# power_node.net
KiCad netlist of a schematic drawn in EAGLE
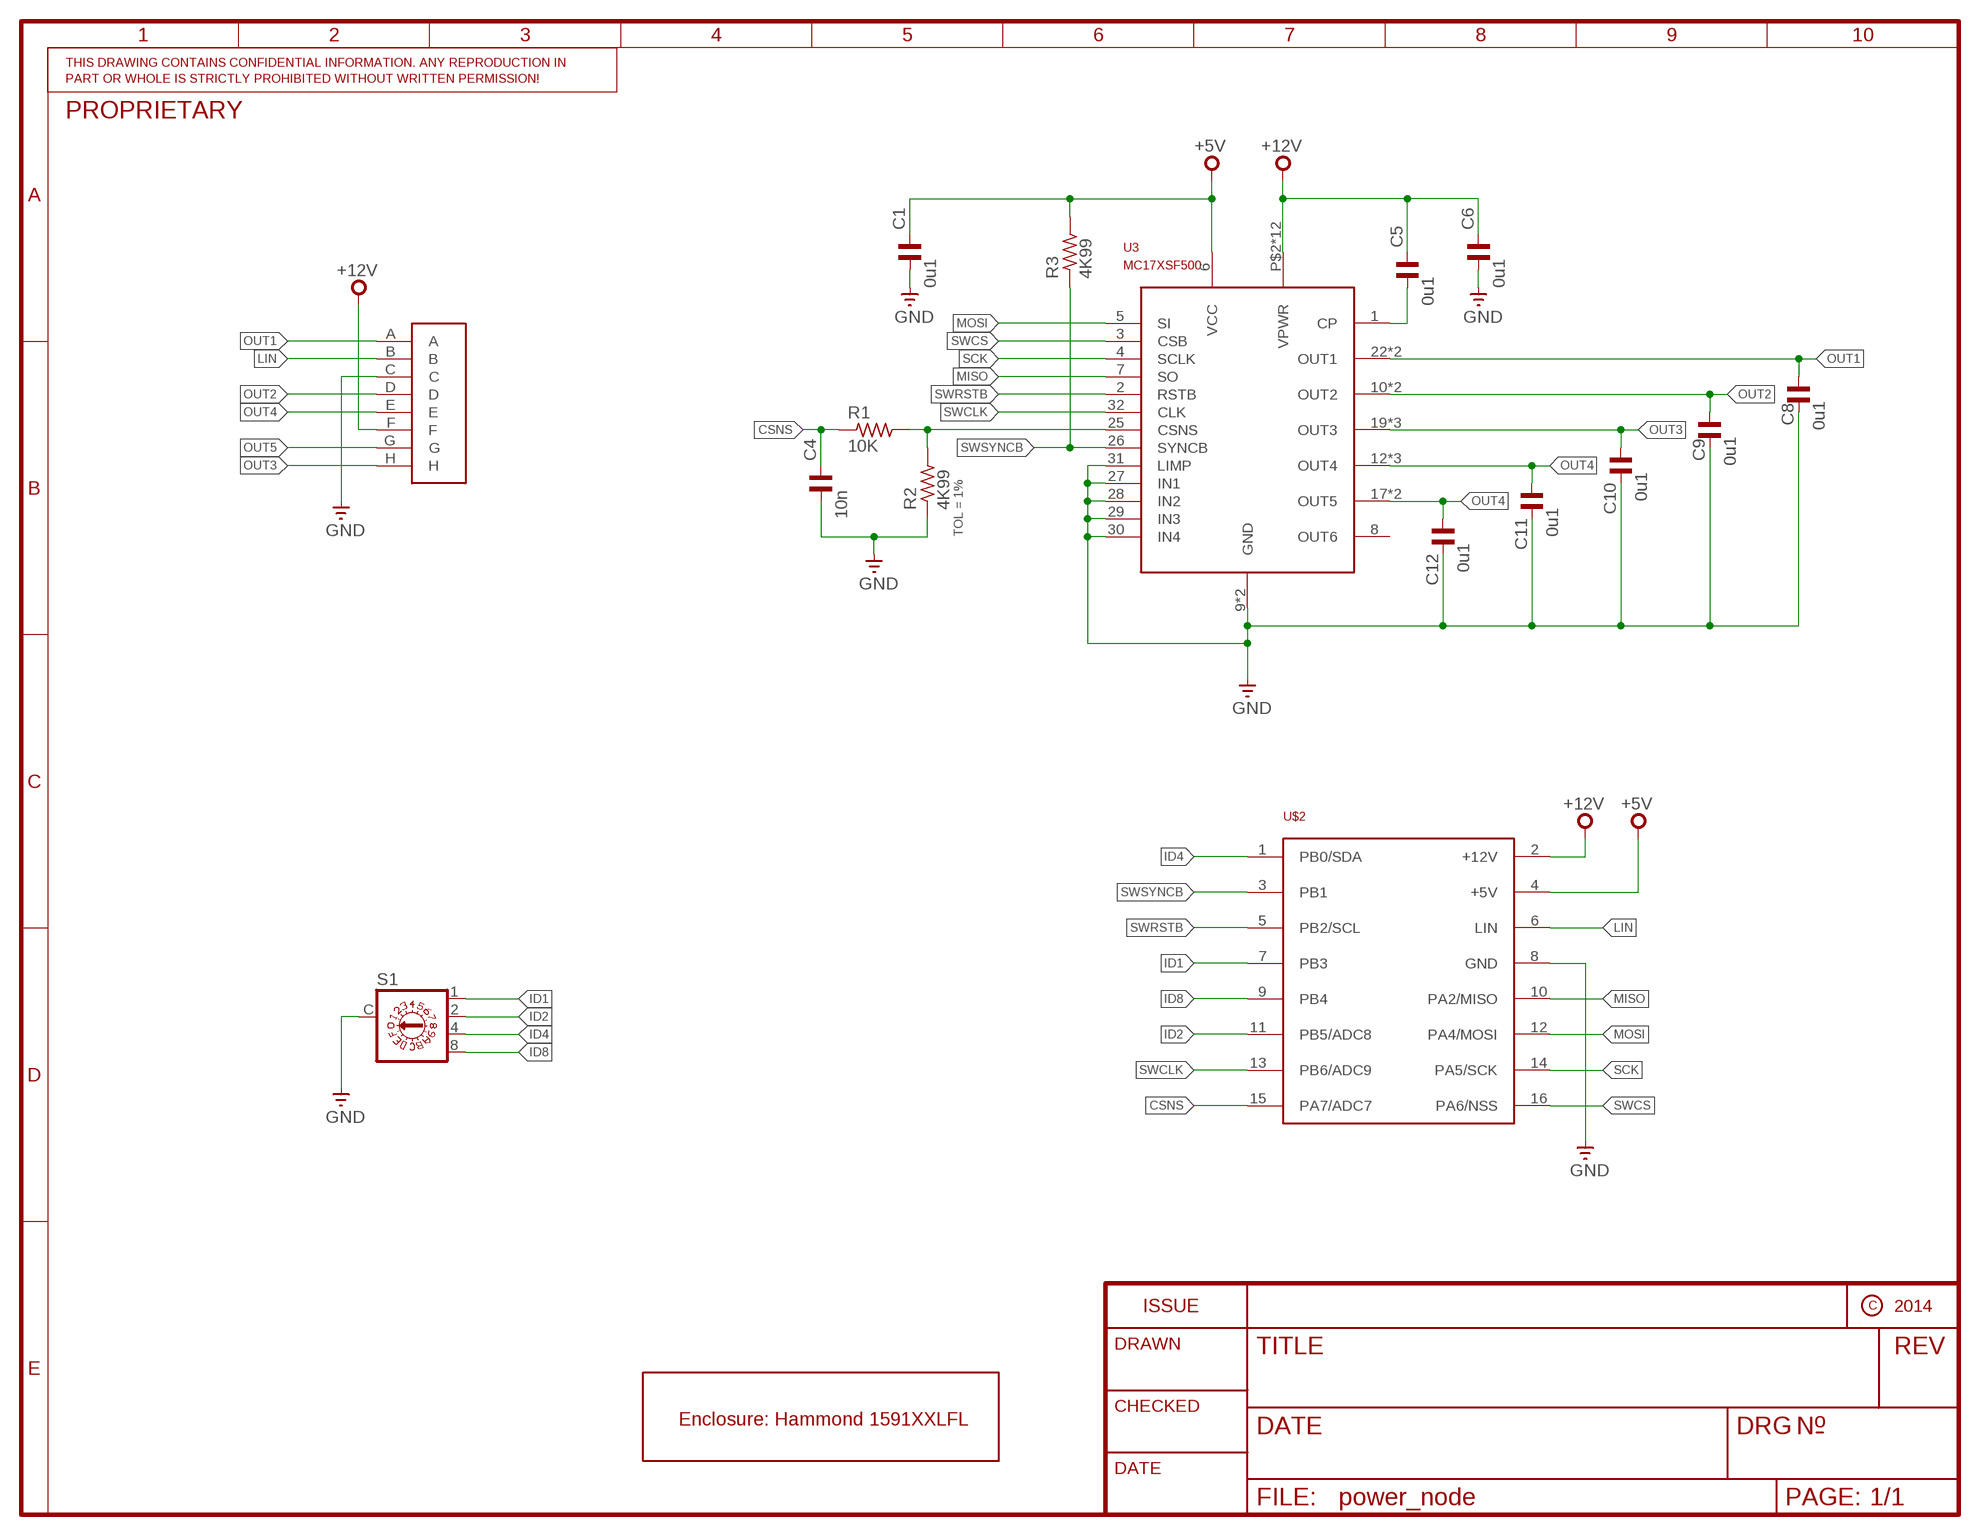
[diagram p0: schematic, sheet 1]

(export (version "E")
  (design (tool "Eeschema 10.0.6"))
  (components
    (comp (ref "C1")
      (value "0u1")
      (footprint "eagle-import:C0805K")
      (fields (field (name "PARTNO") "FK28X7R1H104K"))
      (libsource (lib "eagle-import") (part "C-EUC0805K"))
    )
    (comp (ref "C4")
      (value "10n")
      (footprint "eagle-import:C0805K")
      (fields (field (name "PARTNO") "FK18X7R1H103K"))
      (libsource (lib "eagle-import") (part "C-EUC0805K"))
    )
    (comp (ref "C5")
      (value "0u1")
      (footprint "eagle-import:C0805K")
      (fields (field (name "PARTNO") "FK28X7R1H104K"))
      (libsource (lib "eagle-import") (part "C-EUC0805K"))
    )
    (comp (ref "C6")
      (value "0u1")
      (footprint "eagle-import:C0805K")
      (fields (field (name "PARTNO") "FK28X7R1H104K"))
      (libsource (lib "eagle-import") (part "C-EUC0805K"))
    )
    (comp (ref "C8")
      (value "0u1")
      (footprint "eagle-import:C0805K")
      (fields (field (name "PARTNO") "C1608X7R1H104M080AA"))
      (libsource (lib "eagle-import") (part "C-EUC0805K"))
    )
    (comp (ref "C9")
      (value "0u1")
      (footprint "eagle-import:C0805K")
      (fields (field (name "PARTNO") "C1608X7R1H104M080AA"))
      (libsource (lib "eagle-import") (part "C-EUC0805K"))
    )
    (comp (ref "C10")
      (value "0u1")
      (footprint "eagle-import:C0805K")
      (fields (field (name "PARTNO") "C1608X7R1H104M080AA"))
      (libsource (lib "eagle-import") (part "C-EUC0805K"))
    )
    (comp (ref "C11")
      (value "0u1")
      (footprint "eagle-import:C0805K")
      (fields (field (name "PARTNO") "C1608X7R1H104M080AA"))
      (libsource (lib "eagle-import") (part "C-EUC0805K"))
    )
    (comp (ref "C12")
      (value "0u1")
      (footprint "eagle-import:C0805K")
      (fields (field (name "PARTNO") "C1608X7R1H104M080AA"))
      (libsource (lib "eagle-import") (part "C-EUC0805K"))
    )
    (comp (ref "J2")
      (value "12146734")
      (footprint "eagle-import:12146734")
      (fields (field (name "PARTNO") "12146724-B"))
      (libsource (lib "eagle-import") (part "12146734"))
    )
    (comp (ref "R1")
      (value "10K")
      (footprint "eagle-import:R0805W")
      (fields (field (name "PARTNO") "CF14JT10K0"))
      (libsource (lib "eagle-import") (part "R-EU_R0805W"))
    )
    (comp (ref "R2")
      (value "4K99")
      (footprint "eagle-import:R0805W")
      (fields (field (name "PARTNO") "MFR-25FBF52-4K99") (field (name "TOL") "1%"))
      (libsource (lib "eagle-import") (part "R-EU_R0805W"))
    )
    (comp (ref "R3")
      (value "4K99")
      (footprint "eagle-import:R0805W")
      (fields (field (name "PARTNO") "MFR-25FBF52-4K99"))
      (libsource (lib "eagle-import") (part "R-EU_R0805W"))
    )
    (comp (ref "S1")
      (value "P103")
      (footprint "eagle-import:P103")
      (fields (field (name "PARTNO") "SH-7050MC"))
      (libsource (lib "eagle-import") (part "P103"))
    )
    (comp (ref "U$1")
      (value "1591XXLFL")
      (footprint "eagle-import:1591XXLFL")
      (fields (field (name "PARTNO") "1591XXLFLBK"))
      (libsource (lib "eagle-import") (part "1591XXLFL"))
    )
    (comp (ref "U$2")
      (value "LIN_NODEHORIZ")
      (footprint "eagle-import:LIN_NODE")
      (libsource (lib "eagle-import") (part "LIN_NODEHORIZ"))
    )
    (comp (ref "U3")
      (value "MC17XSF500")
      (footprint "eagle-import:SOIC32W-EP")
      (fields (field (name "PARTNO") "MC17XSF500EK"))
      (libsource (lib "eagle-import") (part "MC17XSF500"))
    )
  )
  (nets
    (net (code "1") (name "+5V") (class "Default")
      (node (ref "C1") (pin "1") (pinfunction "1_1") (pintype "passive"))
      (node (ref "R3") (pin "2") (pinfunction "2_2") (pintype "passive"))
      (node (ref "U$2") (pin "4") (pinfunction "+5V_4") (pintype "power_in"))
      (node (ref "U3") (pin "6") (pinfunction "VCC_6") (pintype "power_in"))
    )
    (net (code "2") (name "+12V") (class "Default")
      (node (ref "C5") (pin "1") (pinfunction "1_1") (pintype "passive"))
      (node (ref "C6") (pin "1") (pinfunction "1_1") (pintype "passive"))
      (node (ref "J2") (pin "F") (pinfunction "F_F") (pintype "bidirectional"))
      (node (ref "U$2") (pin "2") (pinfunction "+12V_2") (pintype "power_in"))
      (node (ref "U3") (pin "P$10") (pinfunction "VPWR_P$10") (pintype "power_in"))
      (node (ref "U3") (pin "P$11") (pinfunction "VPWR_P$11") (pintype "power_in"))
      (node (ref "U3") (pin "P$12") (pinfunction "VPWR_P$12") (pintype "power_in"))
      (node (ref "U3") (pin "P$13") (pinfunction "VPWR_P$13") (pintype "power_in"))
      (node (ref "U3") (pin "P$2") (pinfunction "VPWR_P$2") (pintype "power_in"))
      (node (ref "U3") (pin "P$3") (pinfunction "VPWR_P$3") (pintype "power_in"))
      (node (ref "U3") (pin "P$4") (pinfunction "VPWR_P$4") (pintype "power_in"))
      (node (ref "U3") (pin "P$5") (pinfunction "VPWR_P$5") (pintype "power_in"))
      (node (ref "U3") (pin "P$6") (pinfunction "VPWR_P$6") (pintype "power_in"))
      (node (ref "U3") (pin "P$7") (pinfunction "VPWR_P$7") (pintype "power_in"))
      (node (ref "U3") (pin "P$8") (pinfunction "VPWR_P$8") (pintype "power_in"))
      (node (ref "U3") (pin "P$9") (pinfunction "VPWR_P$9") (pintype "power_in"))
    )
    (net (code "3") (name "CSNS") (class "Default")
      (node (ref "C4") (pin "1") (pinfunction "1_1") (pintype "passive"))
      (node (ref "R1") (pin "1") (pinfunction "1_1") (pintype "passive"))
      (node (ref "U$2") (pin "15") (pinfunction "PA7/ADC7_15") (pintype "bidirectional"))
    )
    (net (code "4") (name "GND") (class "Default")
      (node (ref "C1") (pin "2") (pinfunction "2_2") (pintype "passive"))
      (node (ref "C10") (pin "2") (pinfunction "2_2") (pintype "passive"))
      (node (ref "C11") (pin "2") (pinfunction "2_2") (pintype "passive"))
      (node (ref "C12") (pin "2") (pinfunction "2_2") (pintype "passive"))
      (node (ref "C4") (pin "2") (pinfunction "2_2") (pintype "passive"))
      (node (ref "C6") (pin "2") (pinfunction "2_2") (pintype "passive"))
      (node (ref "C8") (pin "2") (pinfunction "2_2") (pintype "passive"))
      (node (ref "C9") (pin "2") (pinfunction "2_2") (pintype "passive"))
      (node (ref "J2") (pin "C") (pinfunction "C_C") (pintype "bidirectional"))
      (node (ref "R2") (pin "1") (pinfunction "1_1") (pintype "passive"))
      (node (ref "S1") (pin "C") (pinfunction "C_C") (pintype "passive"))
      (node (ref "U$2") (pin "8") (pinfunction "GND_8") (pintype "power_in"))
      (node (ref "U3") (pin "24") (pinfunction "GND_24") (pintype "power_in"))
      (node (ref "U3") (pin "27") (pinfunction "IN1_27") (pintype "input"))
      (node (ref "U3") (pin "28") (pinfunction "IN2_28") (pintype "input"))
      (node (ref "U3") (pin "29") (pinfunction "IN3_29") (pintype "input"))
      (node (ref "U3") (pin "30") (pinfunction "IN4_30") (pintype "input"))
      (node (ref "U3") (pin "31") (pinfunction "LIMP_31") (pintype "input"))
      (node (ref "U3") (pin "9") (pinfunction "GND_9") (pintype "power_in"))
    )
    (net (code "5") (name "ID1") (class "Default")
      (node (ref "S1") (pin "1") (pinfunction "1_1") (pintype "passive"))
      (node (ref "U$2") (pin "7") (pinfunction "PB3_7") (pintype "bidirectional"))
    )
    (net (code "6") (name "ID2") (class "Default")
      (node (ref "S1") (pin "2") (pinfunction "2_2") (pintype "passive"))
      (node (ref "U$2") (pin "11") (pinfunction "PB5/ADC8_11") (pintype "bidirectional"))
    )
    (net (code "7") (name "ID4") (class "Default")
      (node (ref "S1") (pin "4") (pinfunction "4_4") (pintype "passive"))
      (node (ref "U$2") (pin "1") (pinfunction "PB0/SDA_1") (pintype "bidirectional"))
    )
    (net (code "8") (name "ID8") (class "Default")
      (node (ref "S1") (pin "8") (pinfunction "8_8") (pintype "passive"))
      (node (ref "U$2") (pin "9") (pinfunction "PB4_9") (pintype "bidirectional"))
    )
    (net (code "9") (name "LIN") (class "Default")
      (node (ref "J2") (pin "B") (pinfunction "B_B") (pintype "bidirectional"))
      (node (ref "U$2") (pin "6") (pinfunction "LIN_6") (pintype "bidirectional"))
    )
    (net (code "10") (name "MISO") (class "Default")
      (node (ref "U$2") (pin "10") (pinfunction "PA2/MISO_10") (pintype "bidirectional"))
      (node (ref "U3") (pin "7") (pinfunction "SO_7") (pintype "output"))
    )
    (net (code "11") (name "MOSI") (class "Default")
      (node (ref "U$2") (pin "12") (pinfunction "PA4/MOSI_12") (pintype "bidirectional"))
      (node (ref "U3") (pin "5") (pinfunction "SI_5") (pintype "input"))
    )
    (net (code "12") (name "Net-(U3-CP)") (class "Default")
      (node (ref "C5") (pin "2") (pinfunction "2_2") (pintype "passive"))
      (node (ref "U3") (pin "1") (pinfunction "CP_1") (pintype "passive"))
    )
    (net (code "13") (name "Net-(U3-CSNS)") (class "Default")
      (node (ref "R1") (pin "2") (pinfunction "2_2") (pintype "passive"))
      (node (ref "R2") (pin "2") (pinfunction "2_2") (pintype "passive"))
      (node (ref "U3") (pin "25") (pinfunction "CSNS_25") (pintype "output"))
    )
    (net (code "14") (name "OUT1") (class "Default")
      (node (ref "C8") (pin "1") (pinfunction "1_1") (pintype "passive"))
      (node (ref "J2") (pin "A") (pinfunction "A_A") (pintype "bidirectional"))
      (node (ref "U3") (pin "22") (pinfunction "OUT1_22") (pintype "output"))
      (node (ref "U3") (pin "23") (pinfunction "OUT1_23") (pintype "output"))
    )
    (net (code "15") (name "OUT2") (class "Default")
      (node (ref "C9") (pin "1") (pinfunction "1_1") (pintype "passive"))
      (node (ref "J2") (pin "D") (pinfunction "D_D") (pintype "bidirectional"))
      (node (ref "U3") (pin "10") (pinfunction "OUT2_10") (pintype "output"))
      (node (ref "U3") (pin "11") (pinfunction "OUT2_11") (pintype "output"))
    )
    (net (code "16") (name "OUT3") (class "Default")
      (node (ref "C10") (pin "1") (pinfunction "1_1") (pintype "passive"))
      (node (ref "J2") (pin "H") (pinfunction "H_H") (pintype "bidirectional"))
      (node (ref "U3") (pin "19") (pinfunction "OUT3_19") (pintype "output"))
      (node (ref "U3") (pin "20") (pinfunction "OUT3_20") (pintype "output"))
      (node (ref "U3") (pin "21") (pinfunction "OUT3_21") (pintype "output"))
    )
    (net (code "17") (name "OUT4") (class "Default")
      (node (ref "C11") (pin "1") (pinfunction "1_1") (pintype "passive"))
      (node (ref "J2") (pin "E") (pinfunction "E_E") (pintype "bidirectional"))
      (node (ref "U3") (pin "12") (pinfunction "OUT4_12") (pintype "output"))
      (node (ref "U3") (pin "13") (pinfunction "OUT4_13") (pintype "output"))
      (node (ref "U3") (pin "14") (pinfunction "OUT4_14") (pintype "output"))
    )
    (net (code "18") (name "OUT5") (class "Default")
      (node (ref "C12") (pin "1") (pinfunction "1_1") (pintype "passive"))
      (node (ref "J2") (pin "G") (pinfunction "G_G") (pintype "bidirectional"))
      (node (ref "U3") (pin "17") (pinfunction "OUT5_17") (pintype "output"))
      (node (ref "U3") (pin "18") (pinfunction "OUT5_18") (pintype "output"))
    )
    (net (code "19") (name "SCK") (class "Default")
      (node (ref "U$2") (pin "14") (pinfunction "PA5/SCK_14") (pintype "bidirectional"))
      (node (ref "U3") (pin "4") (pinfunction "SCLK_4") (pintype "input"))
    )
    (net (code "20") (name "SWCLK") (class "Default")
      (node (ref "U$2") (pin "13") (pinfunction "PB6/ADC9_13") (pintype "bidirectional"))
      (node (ref "U3") (pin "32") (pinfunction "CLK_32") (pintype "bidirectional"))
    )
    (net (code "21") (name "SWCS") (class "Default")
      (node (ref "U$2") (pin "16") (pinfunction "PA6/NSS_16") (pintype "bidirectional"))
      (node (ref "U3") (pin "3") (pinfunction "CSB_3") (pintype "input"))
    )
    (net (code "22") (name "SWRSTB") (class "Default")
      (node (ref "U$2") (pin "5") (pinfunction "PB2/SCL_5") (pintype "bidirectional"))
      (node (ref "U3") (pin "2") (pinfunction "RSTB_2") (pintype "input"))
    )
    (net (code "23") (name "SWSYNCB") (class "Default")
      (node (ref "R3") (pin "1") (pinfunction "1_1") (pintype "passive"))
      (node (ref "U$2") (pin "3") (pinfunction "PB1_3") (pintype "bidirectional"))
      (node (ref "U3") (pin "26") (pinfunction "SYNCB_26") (pintype "open_collector"))
    )
    (net (code "24") (name "unconnected-(U3-OUT6-Pad8)") (class "Default")
      (node (ref "U3") (pin "8") (pinfunction "OUT6_8") (pintype "output"))
    )
  )
)
